# trot_activateur_ES200.net
KiCad netlist of a schematic drawn in EAGLE
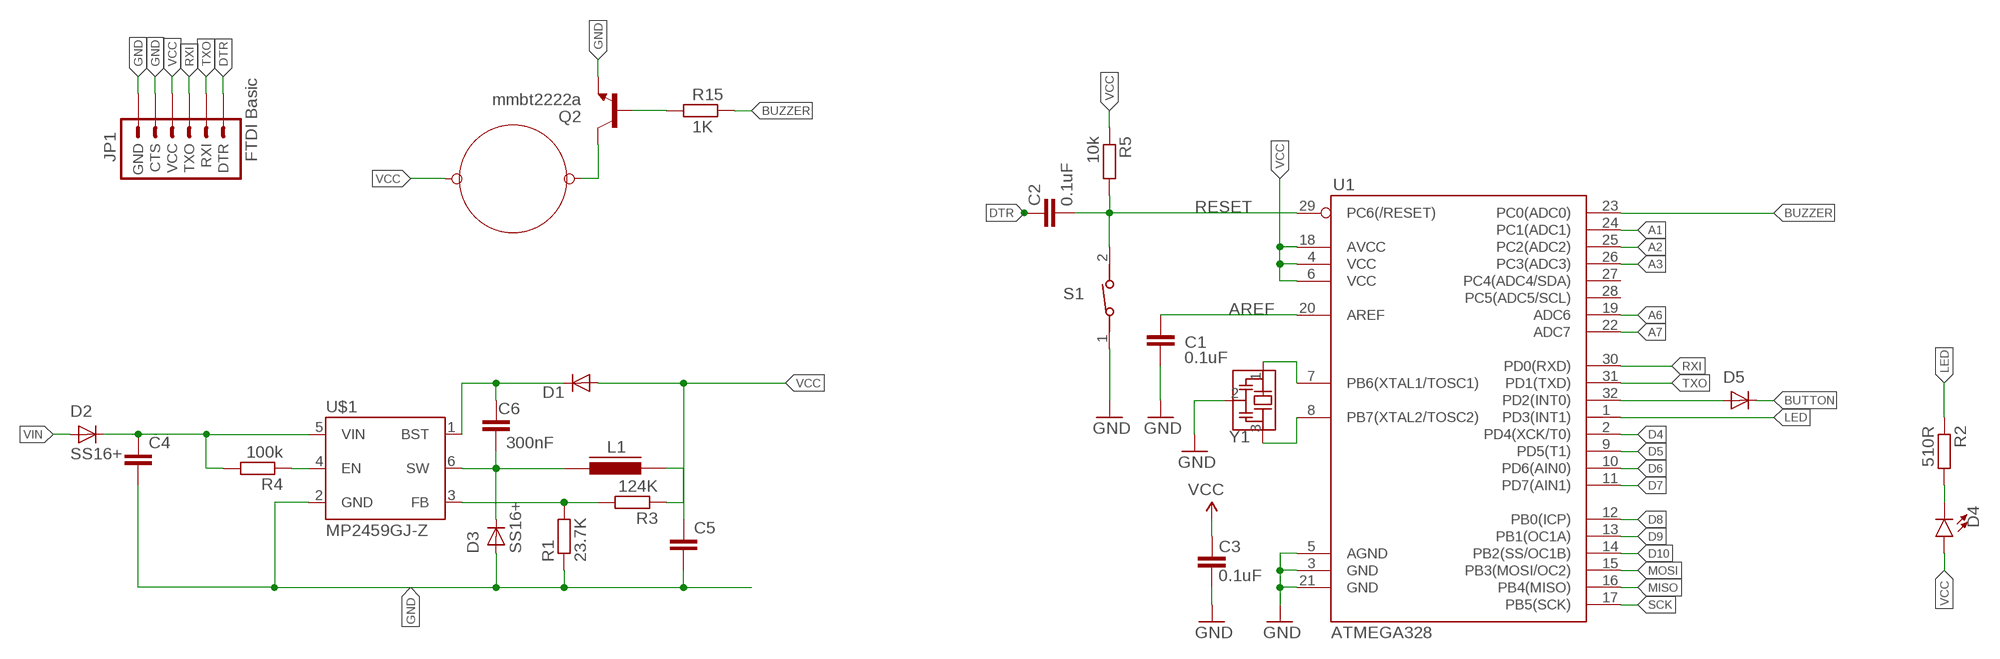
[diagram p0: schematic, sheet 1]

(export (version "E")
  (design (tool "Eeschema 10.0.6"))
  (components
    (comp (ref "C1")
      (value "0.1uF")
      (footprint "eagle-import:C0603")
      (libsource (lib "eagle-import") (part "C-EUC0603"))
    )
    (comp (ref "C2")
      (value "0.1uF")
      (footprint "eagle-import:C0603")
      (libsource (lib "eagle-import") (part "C-EUC0603"))
    )
    (comp (ref "C3")
      (value "0.1uF")
      (footprint "eagle-import:C0603")
      (libsource (lib "eagle-import") (part "C-EUC0603"))
    )
    (comp (ref "C4")
      (value "4.7uF; X7R; 50V")
      (footprint "eagle-import:C1210")
      (libsource (lib "eagle-import") (part "C-EUC1210"))
    )
    (comp (ref "C5")
      (value "22uF;X7R;10V")
      (footprint "eagle-import:C1210")
      (libsource (lib "eagle-import") (part "C-EUC1210"))
    )
    (comp (ref "C6")
      (value "300nF")
      (footprint "eagle-import:C0603")
      (libsource (lib "eagle-import") (part "C-EUC0603"))
    )
    (comp (ref "D1")
      (value "1N4148W RH")
      (footprint "eagle-import:SOD123")
      (libsource (lib "eagle-import") (part "DIODE-SOD123"))
    )
    (comp (ref "D2")
      (value "SS16+")
      (footprint "eagle-import:SMA-DO214AC")
      (libsource (lib "eagle-import") (part "GF1"))
    )
    (comp (ref "D3")
      (value "SS16+")
      (footprint "eagle-import:SMA-DO214AC")
      (libsource (lib "eagle-import") (part "GF1"))
    )
    (comp (ref "D4")
      (value "LED0603")
      (footprint "eagle-import:LED-0603")
      (libsource (lib "eagle-import") (part "LED0603"))
    )
    (comp (ref "D5")
      (value "SS16+")
      (footprint "eagle-import:SMA-DO214AC")
      (libsource (lib "eagle-import") (part "GF1"))
    )
    (comp (ref "JP1")
      (value "FTDI Basic")
      (footprint "eagle-import:1X06")
      (libsource (lib "eagle-import") (part "ARDUINO_SERIAL_PROGRAMPTH"))
    )
    (comp (ref "L1")
      (value "VLS5045EX-151M")
      (footprint "eagle-import:VLS5045EX")
      (libsource (lib "eagle-import") (part "VLS5045EX"))
    )
    (comp (ref "Q2")
      (value "mmbt2222a")
      (footprint "eagle-import:SPARKFUN_SOT23-3")
      (libsource (lib "eagle-import") (part "SPARKFUN_TRANSISTOR_NPNSOT23-3"))
    )
    (comp (ref "R1")
      (value "23.7K")
      (footprint "eagle-import:R0603")
      (libsource (lib "eagle-import") (part "R-EU_R0603"))
    )
    (comp (ref "R2")
      (value "510R")
      (footprint "eagle-import:R0603")
      (libsource (lib "eagle-import") (part "rcl_custom_26985561_R-EU_R0603"))
    )
    (comp (ref "R3")
      (value "124K")
      (footprint "eagle-import:R0603")
      (libsource (lib "eagle-import") (part "R-EU_R0603"))
    )
    (comp (ref "R4")
      (value "100k")
      (footprint "eagle-import:R0603")
      (libsource (lib "eagle-import") (part "rcl_custom_26985561_R-EU_R0603"))
    )
    (comp (ref "R5")
      (value "10k")
      (footprint "eagle-import:R0603")
      (libsource (lib "eagle-import") (part "rcl_custom_26985561_R-EU_R0603"))
    )
    (comp (ref "R15")
      (value "1K")
      (footprint "eagle-import:R0603")
      (libsource (lib "eagle-import") (part "rcl_custom_26985561_R-EU_R0603"))
    )
    (comp (ref "S1")
      (value "434113025826")
      (footprint "eagle-import:434113025826")
      (libsource (lib "eagle-import") (part "434113025826"))
    )
    (comp (ref "U$1")
      (value "MP2459GJ-Z")
      (footprint "eagle-import:SOT23-6")
      (libsource (lib "eagle-import") (part "MP2459GJ-Z"))
    )
    (comp (ref "U$6")
      (value "BUZZER-KPX-G1203UB")
      (footprint "eagle-import:BUZZER-KPX-G1203UB")
      (libsource (lib "eagle-import") (part "BUZZER-KPX-G1203UB"))
    )
    (comp (ref "U1")
      (value "ATMEGA328")
      (footprint "eagle-import:SPARKFUN_TQFP32-08")
      (libsource (lib "eagle-import") (part "SPARKFUN_ATMEGA168"))
    )
    (comp (ref "Y1")
      (value "CSTNE16M0V530000R0")
      (footprint "eagle-import:OSC_CSTNE16M0V530000R0")
      (fields (field (name "MF") "Murata Electronics"))
      (libsource (lib "eagle-import") (part "CSTNE16M0V530000R0"))
    )
  )
  (nets
    (net (code "1") (name "/AREF") (class "Default")
      (node (ref "C1") (pin "2") (pinfunction "2_2") (pintype "passive"))
      (node (ref "U1") (pin "20") (pinfunction "AREF_20") (pintype "bidirectional"))
    )
    (net (code "2") (name "/RESET") (class "Default")
      (node (ref "C2") (pin "1") (pinfunction "1_1") (pintype "passive"))
      (node (ref "R5") (pin "2") (pinfunction "2_2") (pintype "passive"))
      (node (ref "S1") (pin "2") (pinfunction "2_2") (pintype "passive"))
      (node (ref "U1") (pin "29") (pinfunction "PC6(/RESET)_29") (pintype "bidirectional"))
    )
    (net (code "3") (name "A1") (class "Default")
      (node (ref "U1") (pin "24") (pinfunction "PC1(ADC1)_24") (pintype "bidirectional"))
    )
    (net (code "4") (name "A2") (class "Default")
      (node (ref "U1") (pin "25") (pinfunction "PC2(ADC2)_25") (pintype "bidirectional"))
    )
    (net (code "5") (name "A3") (class "Default")
      (node (ref "U1") (pin "26") (pinfunction "PC3(ADC3)_26") (pintype "bidirectional"))
    )
    (net (code "6") (name "A6") (class "Default")
      (node (ref "U1") (pin "19") (pinfunction "ADC6_19") (pintype "bidirectional"))
    )
    (net (code "7") (name "A7") (class "Default")
      (node (ref "U1") (pin "22") (pinfunction "ADC7_22") (pintype "bidirectional"))
    )
    (net (code "8") (name "BUTTON") (class "Default")
      (node (ref "D5") (pin "K") (pinfunction "C_K") (pintype "passive"))
    )
    (net (code "9") (name "BUZZER") (class "Default")
      (node (ref "R15") (pin "2") (pinfunction "2_2") (pintype "passive"))
      (node (ref "U1") (pin "23") (pinfunction "PC0(ADC0)_23") (pintype "bidirectional"))
    )
    (net (code "10") (name "D4") (class "Default")
      (node (ref "U1") (pin "2") (pinfunction "PD4(XCK/T0)_2") (pintype "bidirectional"))
    )
    (net (code "11") (name "D5") (class "Default")
      (node (ref "U1") (pin "9") (pinfunction "PD5(T1)_9") (pintype "bidirectional"))
    )
    (net (code "12") (name "D6") (class "Default")
      (node (ref "U1") (pin "10") (pinfunction "PD6(AIN0)_10") (pintype "bidirectional"))
    )
    (net (code "13") (name "D7") (class "Default")
      (node (ref "U1") (pin "11") (pinfunction "PD7(AIN1)_11") (pintype "bidirectional"))
    )
    (net (code "14") (name "D8") (class "Default")
      (node (ref "U1") (pin "12") (pinfunction "PB0(ICP)_12") (pintype "bidirectional"))
    )
    (net (code "15") (name "D9") (class "Default")
      (node (ref "U1") (pin "13") (pinfunction "PB1(OC1A)_13") (pintype "bidirectional"))
    )
    (net (code "16") (name "D10") (class "Default")
      (node (ref "U1") (pin "14") (pinfunction "PB2(SS/OC1B)_14") (pintype "bidirectional"))
    )
    (net (code "17") (name "DTR") (class "Default")
      (node (ref "C2") (pin "2") (pinfunction "2_2") (pintype "passive"))
      (node (ref "JP1") (pin "1") (pinfunction "DTR_1") (pintype "passive"))
    )
    (net (code "18") (name "GND") (class "Default")
      (node (ref "C1") (pin "1") (pinfunction "1_1") (pintype "passive"))
      (node (ref "C3") (pin "1") (pinfunction "1_1") (pintype "passive"))
      (node (ref "C4") (pin "2") (pinfunction "2_2") (pintype "passive"))
      (node (ref "C5") (pin "2") (pinfunction "2_2") (pintype "passive"))
      (node (ref "D3") (pin "A") (pinfunction "A_A") (pintype "passive"))
      (node (ref "JP1") (pin "5") (pinfunction "CTS_5") (pintype "passive"))
      (node (ref "JP1") (pin "6") (pinfunction "GND_6") (pintype "passive"))
      (node (ref "Q2") (pin "2") (pinfunction "E_2") (pintype "passive"))
      (node (ref "R1") (pin "1") (pinfunction "1_1") (pintype "passive"))
      (node (ref "S1") (pin "1") (pinfunction "1_1") (pintype "passive"))
      (node (ref "U$1") (pin "2") (pinfunction "GND_2") (pintype "power_in"))
      (node (ref "U1") (pin "21") (pinfunction "GND_21") (pintype "bidirectional"))
      (node (ref "U1") (pin "3") (pinfunction "GND_3") (pintype "bidirectional"))
      (node (ref "U1") (pin "5") (pinfunction "AGND_5") (pintype "bidirectional"))
      (node (ref "Y1") (pin "2") (pinfunction "GND_2") (pintype "power_in"))
    )
    (net (code "19") (name "LED") (class "Default")
      (node (ref "R2") (pin "1") (pinfunction "1_1") (pintype "passive"))
      (node (ref "U1") (pin "1") (pinfunction "PD3(INT1)_1") (pintype "bidirectional"))
    )
    (net (code "20") (name "MISO") (class "Default")
      (node (ref "U1") (pin "16") (pinfunction "PB4(MISO)_16") (pintype "bidirectional"))
    )
    (net (code "21") (name "MOSI") (class "Default")
      (node (ref "U1") (pin "15") (pinfunction "PB3(MOSI/OC2)_15") (pintype "bidirectional"))
    )
    (net (code "22") (name "Net-(D2-C)") (class "Default")
      (node (ref "C4") (pin "1") (pinfunction "1_1") (pintype "passive"))
      (node (ref "D2") (pin "K") (pinfunction "C_K") (pintype "passive"))
      (node (ref "R4") (pin "2") (pinfunction "2_2") (pintype "passive"))
      (node (ref "U$1") (pin "5") (pinfunction "VIN_5") (pintype "power_in"))
    )
    (net (code "23") (name "Net-(D3-C)") (class "Default")
      (node (ref "C6") (pin "2") (pinfunction "2_2") (pintype "passive"))
      (node (ref "D3") (pin "K") (pinfunction "C_K") (pintype "passive"))
      (node (ref "L1") (pin "P$1") (pinfunction "1_P$1") (pintype "passive"))
      (node (ref "U$1") (pin "6") (pinfunction "SW_6") (pintype "output"))
    )
    (net (code "24") (name "Net-(D4-PadC)") (class "Default")
      (node (ref "D4") (pin "C") (pinfunction "C_C") (pintype "passive"))
      (node (ref "R2") (pin "2") (pinfunction "2_2") (pintype "passive"))
    )
    (net (code "25") (name "Net-(Q2-B)") (class "Default")
      (node (ref "Q2") (pin "1") (pinfunction "B_1") (pintype "passive"))
      (node (ref "R15") (pin "1") (pinfunction "1_1") (pintype "passive"))
    )
    (net (code "26") (name "Net-(Q2-C)") (class "Default")
      (node (ref "Q2") (pin "3") (pinfunction "C_3") (pintype "passive"))
      (node (ref "U$6") (pin "P$2") (pinfunction "P$2_P$2") (pintype "bidirectional"))
    )
    (net (code "27") (name "Net-(U$1-BST)") (class "Default")
      (node (ref "C6") (pin "1") (pinfunction "1_1") (pintype "passive"))
      (node (ref "D1") (pin "C") (pinfunction "C_C") (pintype "passive"))
      (node (ref "U$1") (pin "1") (pinfunction "BST_1") (pintype "input"))
    )
    (net (code "28") (name "Net-(U$1-EN)") (class "Default")
      (node (ref "R4") (pin "1") (pinfunction "1_1") (pintype "passive"))
      (node (ref "U$1") (pin "4") (pinfunction "EN_4") (pintype "input"))
    )
    (net (code "29") (name "Net-(U$1-FB)") (class "Default")
      (node (ref "R1") (pin "2") (pinfunction "2_2") (pintype "passive"))
      (node (ref "R3") (pin "2") (pinfunction "2_2") (pintype "passive"))
      (node (ref "U$1") (pin "3") (pinfunction "FB_3") (pintype "power_in"))
    )
    (net (code "30") (name "Net-(U1-PB6(XTAL1{slash}TOSC1))") (class "Default")
      (node (ref "U1") (pin "7") (pinfunction "PB6(XTAL1/TOSC1)_7") (pintype "bidirectional"))
      (node (ref "Y1") (pin "1") (pinfunction "IN_1") (pintype "input"))
    )
    (net (code "31") (name "Net-(U1-PB7(XTAL2{slash}TOSC2))") (class "Default")
      (node (ref "U1") (pin "8") (pinfunction "PB7(XTAL2/TOSC2)_8") (pintype "bidirectional"))
      (node (ref "Y1") (pin "3") (pinfunction "OUT_3") (pintype "output"))
    )
    (net (code "32") (name "Net-(U1-PD2(INT0))") (class "Default")
      (node (ref "D5") (pin "A") (pinfunction "A_A") (pintype "passive"))
      (node (ref "U1") (pin "32") (pinfunction "PD2(INT0)_32") (pintype "bidirectional"))
    )
    (net (code "33") (name "RXI") (class "Default")
      (node (ref "JP1") (pin "3") (pinfunction "TXO_3") (pintype "passive"))
      (node (ref "U1") (pin "30") (pinfunction "PD0(RXD)_30") (pintype "bidirectional"))
    )
    (net (code "34") (name "SCK") (class "Default")
      (node (ref "U1") (pin "17") (pinfunction "PB5(SCK)_17") (pintype "bidirectional"))
    )
    (net (code "35") (name "TXO") (class "Default")
      (node (ref "JP1") (pin "2") (pinfunction "RXI_2") (pintype "passive"))
      (node (ref "U1") (pin "31") (pinfunction "PD1(TXD)_31") (pintype "bidirectional"))
    )
    (net (code "36") (name "VCC") (class "Default")
      (node (ref "C3") (pin "2") (pinfunction "2_2") (pintype "passive"))
      (node (ref "C5") (pin "1") (pinfunction "1_1") (pintype "passive"))
      (node (ref "D1") (pin "A") (pinfunction "A_A") (pintype "passive"))
      (node (ref "D4") (pin "A") (pinfunction "A_A") (pintype "passive"))
      (node (ref "JP1") (pin "4") (pinfunction "VCC_4") (pintype "passive"))
      (node (ref "L1") (pin "P$2") (pinfunction "2_P$2") (pintype "passive"))
      (node (ref "R3") (pin "1") (pinfunction "1_1") (pintype "passive"))
      (node (ref "R5") (pin "1") (pinfunction "1_1") (pintype "passive"))
      (node (ref "U$6") (pin "P$1") (pinfunction "P$1_P$1") (pintype "bidirectional"))
      (node (ref "U1") (pin "18") (pinfunction "AVCC_18") (pintype "bidirectional"))
      (node (ref "U1") (pin "4") (pinfunction "VCC_4") (pintype "bidirectional"))
      (node (ref "U1") (pin "6") (pinfunction "VCC_6") (pintype "bidirectional"))
    )
    (net (code "37") (name "VIN") (class "Default")
      (node (ref "D2") (pin "A") (pinfunction "A_A") (pintype "passive"))
    )
    (net (code "38") (name "unconnected-(U1-PC4(ADC4{slash}SDA)-Pad27)") (class "Default")
      (node (ref "U1") (pin "27") (pinfunction "PC4(ADC4/SDA)_27") (pintype "bidirectional"))
    )
    (net (code "39") (name "unconnected-(U1-PC5(ADC5{slash}SCL)-Pad28)") (class "Default")
      (node (ref "U1") (pin "28") (pinfunction "PC5(ADC5/SCL)_28") (pintype "bidirectional"))
    )
  )
)
